# avr_switch_v09.net
KiCad netlist of a schematic drawn in EAGLE
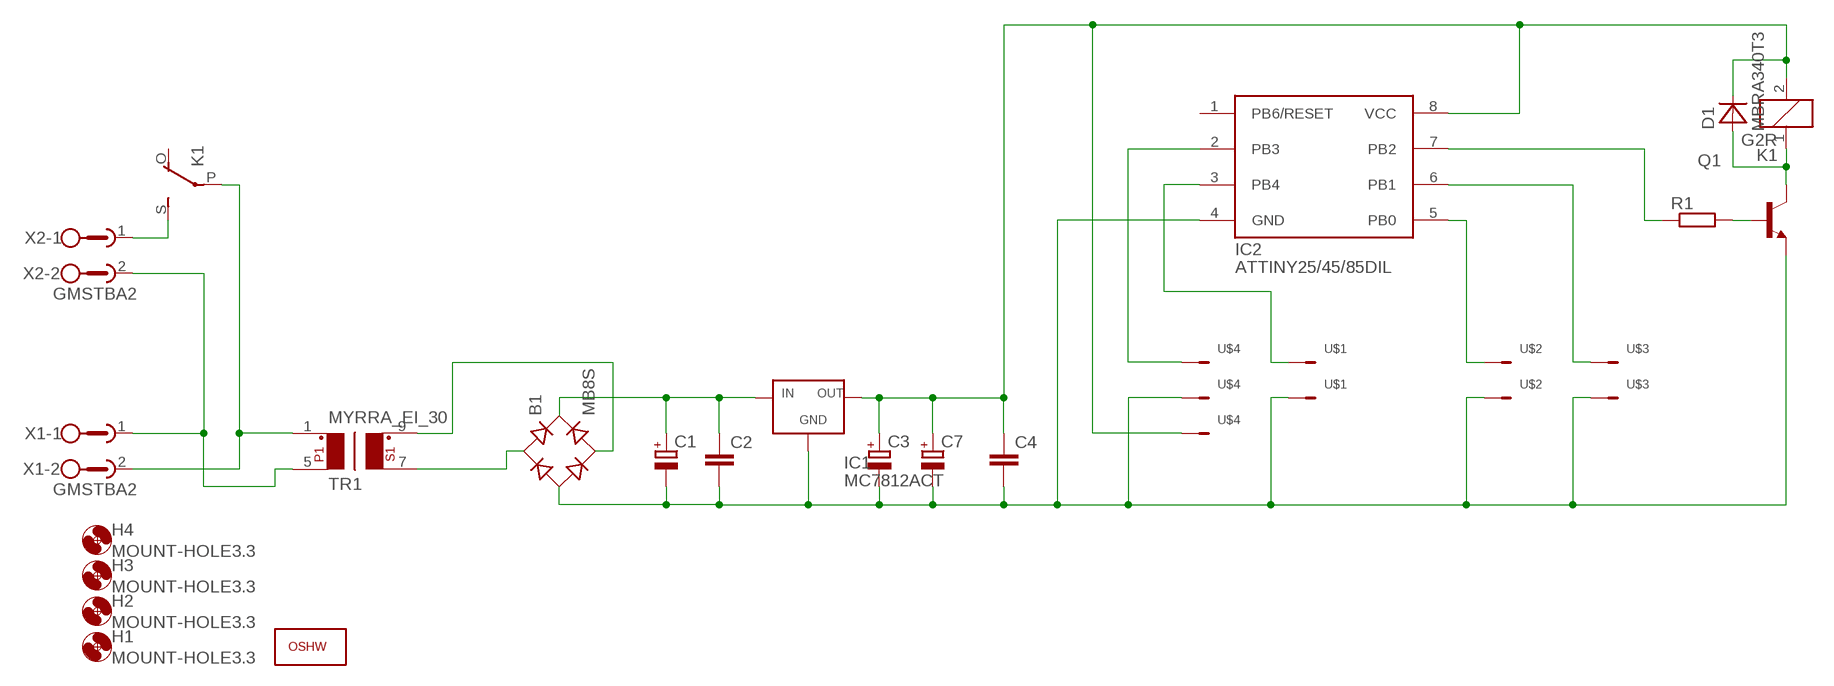
[diagram p0: schematic, sheet 1]

(export (version "E")
  (design (tool "Eeschema 10.0.6"))
  (components
    (comp (ref "B1")
      (value "MB8S")
      (footprint "eagle-import:SOIC-4")
      (libsource (lib "eagle-import") (part "MBS8"))
    )
    (comp (ref "C1")
      (value "CPOL-EUE5-10.5")
      (footprint "eagle-import:E5-10,5")
      (libsource (lib "eagle-import") (part "CPOL-EUE5-10.5"))
    )
    (comp (ref "C2")
      (value "C-EUC0805")
      (footprint "eagle-import:C0805")
      (libsource (lib "eagle-import") (part "C-EUC0805"))
    )
    (comp (ref "C3")
      (value "CPOL-EUCT6032")
      (footprint "eagle-import:CT6032")
      (libsource (lib "eagle-import") (part "CPOL-EUCT6032"))
    )
    (comp (ref "C4")
      (value "C-EUC0805")
      (footprint "eagle-import:C0805")
      (libsource (lib "eagle-import") (part "C-EUC0805"))
    )
    (comp (ref "C7")
      (value "CPOL-EUD/7343-31W")
      (footprint "eagle-import:D_7343-31W")
      (libsource (lib "eagle-import") (part "CPOL-EUD/7343-31W"))
    )
    (comp (ref "D1")
      (value "MBRA340T3")
      (footprint "eagle-import:SMA")
      (libsource (lib "eagle-import") (part "MBRA340T3"))
    )
    (comp (ref "H1")
      (value "MOUNT-HOLE3.3")
      (footprint "eagle-import:3,3")
      (libsource (lib "eagle-import") (part "MOUNT-HOLE3.3"))
    )
    (comp (ref "H2")
      (value "MOUNT-HOLE3.3")
      (footprint "eagle-import:3,3")
      (libsource (lib "eagle-import") (part "MOUNT-HOLE3.3"))
    )
    (comp (ref "H3")
      (value "MOUNT-HOLE3.3")
      (footprint "eagle-import:3,3")
      (libsource (lib "eagle-import") (part "MOUNT-HOLE3.3"))
    )
    (comp (ref "H4")
      (value "MOUNT-HOLE3.3")
      (footprint "eagle-import:3,3")
      (libsource (lib "eagle-import") (part "MOUNT-HOLE3.3"))
    )
    (comp (ref "IC1")
      (value "MC7812ACT")
      (footprint "eagle-import:TO220V")
      (libsource (lib "eagle-import") (part "MC7812ACT"))
    )
    (comp (ref "IC2")
      (value "ATTINY25/45/85DIL")
      (footprint "eagle-import:DIL08")
      (libsource (lib "eagle-import") (part "ATTINY25/45/85DIL"))
    )
    (comp (ref "K1")
      (value "G2R")
      (footprint "eagle-import:G2R")
      (libsource (lib "eagle-import") (part "G2R"))
    )
    (comp (ref "Q1")
      (value "BC548-NPN-TO92-CBE")
      (footprint "eagle-import:TO92-CBE")
      (libsource (lib "eagle-import") (part "-NPN-TO92-CBEBC548"))
    )
    (comp (ref "R1")
      (value "R-EU_R1206")
      (footprint "eagle-import:R1206")
      (libsource (lib "eagle-import") (part "R-EU_R1206"))
    )
    (comp (ref "TR1")
      (value "MYRRA_EI_30")
      (footprint "eagle-import:MYRRA-EI30")
      (libsource (lib "eagle-import") (part "MYRRA_EI_30"))
    )
    (comp (ref "U$1")
      (value "MOLEX-VERT-KK-2-")
      (footprint "eagle-import:MOLEX-KK-VERT-2PIN")
      (libsource (lib "eagle-import") (part "MOLEX-VERT-KK-2-"))
    )
    (comp (ref "U$2")
      (value "MOLEX-VERT-KK-2-")
      (footprint "eagle-import:MOLEX-KK-VERT-2PIN")
      (libsource (lib "eagle-import") (part "MOLEX-VERT-KK-2-"))
    )
    (comp (ref "U$3")
      (value "MOLEX-VERT-KK-2-")
      (footprint "eagle-import:MOLEX-KK-VERT-2PIN")
      (libsource (lib "eagle-import") (part "MOLEX-VERT-KK-2-"))
    )
    (comp (ref "U$4")
      (value "MOLEX-VERT-KK-3-3PIN")
      (footprint "eagle-import:MOLEX-KK-VERT-3PIN")
      (libsource (lib "eagle-import") (part "MOLEX-VERT-KK-3-3PIN"))
    )
    (comp (ref "U$5")
      (value "OSHWOSHW_TOP")
      (footprint "eagle-import:OSHW_F")
      (libsource (lib "eagle-import") (part "OSHWOSHW_TOP"))
    )
    (comp (ref "X1")
      (value "GMSTBA2")
      (footprint "eagle-import:GMSTBA2")
      (fields (field (name "MF") "FARNELL") (field (name "MPN") "1757242"))
      (libsource (lib "eagle-import") (part "GMSTBA2"))
    )
    (comp (ref "X2")
      (value "GMSTBA2")
      (footprint "eagle-import:GMSTBA2")
      (fields (field (name "MF") "FARNELL") (field (name "MPN") "1757242"))
      (libsource (lib "eagle-import") (part "GMSTBA2"))
    )
  )
  (nets
    (net (code "1") (name "Net-(B1-AC1)") (class "Default")
      (node (ref "B1") (pin "~1") (pinfunction "AC1_~1") (pintype "passive"))
      (node (ref "TR1") (pin "7") (pinfunction "7_7") (pintype "passive"))
    )
    (net (code "2") (name "Net-(B1-AC2)") (class "Default")
      (node (ref "B1") (pin "~2") (pinfunction "AC2_~2") (pintype "passive"))
      (node (ref "TR1") (pin "9") (pinfunction "9_9") (pintype "passive"))
    )
    (net (code "3") (name "Net-(D1-PadA)") (class "Default")
      (node (ref "D1") (pin "A") (pinfunction "A_A") (pintype "passive"))
      (node (ref "K1") (pin "1") (pinfunction "1_1") (pintype "passive"))
      (node (ref "Q1") (pin "C") (pinfunction "C_C") (pintype "passive"))
    )
    (net (code "4") (name "Net-(IC1-GND)") (class "Default")
      (node (ref "B1") (pin "-") (pinfunction "-_-") (pintype "passive"))
      (node (ref "C1") (pin "-") (pinfunction "-_-") (pintype "passive"))
      (node (ref "C2") (pin "2") (pinfunction "2_2") (pintype "passive"))
      (node (ref "C3") (pin "-") (pinfunction "-_-") (pintype "passive"))
      (node (ref "C4") (pin "2") (pinfunction "2_2") (pintype "passive"))
      (node (ref "C7") (pin "-") (pinfunction "-_-") (pintype "passive"))
      (node (ref "IC1") (pin "2") (pinfunction "GND_2") (pintype "bidirectional"))
      (node (ref "IC2") (pin "4") (pinfunction "GND_4") (pintype "bidirectional"))
      (node (ref "Q1") (pin "E") (pinfunction "E_E") (pintype "passive"))
      (node (ref "U$1") (pin "1") (pinfunction "P$1_1") (pintype "bidirectional"))
      (node (ref "U$2") (pin "1") (pinfunction "P$1_1") (pintype "bidirectional"))
      (node (ref "U$3") (pin "1") (pinfunction "P$1_1") (pintype "bidirectional"))
      (node (ref "U$4") (pin "2") (pinfunction "P$1_2") (pintype "bidirectional"))
    )
    (net (code "5") (name "Net-(IC1-IN)") (class "Default")
      (node (ref "B1") (pin "+") (pinfunction "+_+") (pintype "passive"))
      (node (ref "C1") (pin "+") (pinfunction "+_+") (pintype "passive"))
      (node (ref "C2") (pin "1") (pinfunction "1_1") (pintype "passive"))
      (node (ref "IC1") (pin "1") (pinfunction "IN_1") (pintype "bidirectional"))
    )
    (net (code "6") (name "Net-(IC1-OUT)") (class "Default")
      (node (ref "C3") (pin "+") (pinfunction "+_+") (pintype "passive"))
      (node (ref "C4") (pin "1") (pinfunction "1_1") (pintype "passive"))
      (node (ref "C7") (pin "+") (pinfunction "+_+") (pintype "passive"))
      (node (ref "D1") (pin "C") (pinfunction "C_C") (pintype "passive"))
      (node (ref "IC1") (pin "3") (pinfunction "OUT_3") (pintype "bidirectional"))
      (node (ref "IC2") (pin "8") (pinfunction "VCC_8") (pintype "bidirectional"))
      (node (ref "K1") (pin "2") (pinfunction "2_2") (pintype "passive"))
      (node (ref "U$4") (pin "1") (pinfunction "P$1_1") (pintype "bidirectional"))
    )
    (net (code "7") (name "Net-(IC2-PB0)") (class "Default")
      (node (ref "IC2") (pin "5") (pinfunction "PB0_5") (pintype "bidirectional"))
      (node (ref "U$2") (pin "2") (pinfunction "P$1_2") (pintype "bidirectional"))
    )
    (net (code "8") (name "Net-(IC2-PB1)") (class "Default")
      (node (ref "IC2") (pin "6") (pinfunction "PB1_6") (pintype "bidirectional"))
      (node (ref "U$3") (pin "2") (pinfunction "P$1_2") (pintype "bidirectional"))
    )
    (net (code "9") (name "Net-(IC2-PB2)") (class "Default")
      (node (ref "IC2") (pin "7") (pinfunction "PB2_7") (pintype "bidirectional"))
      (node (ref "R1") (pin "1") (pinfunction "1_1") (pintype "passive"))
    )
    (net (code "10") (name "Net-(IC2-PB3)") (class "Default")
      (node (ref "IC2") (pin "2") (pinfunction "PB3_2") (pintype "bidirectional"))
      (node (ref "U$4") (pin "3") (pinfunction "P$1_3") (pintype "bidirectional"))
    )
    (net (code "11") (name "Net-(IC2-PB4)") (class "Default")
      (node (ref "IC2") (pin "3") (pinfunction "PB4_3") (pintype "bidirectional"))
      (node (ref "U$1") (pin "2") (pinfunction "P$1_2") (pintype "bidirectional"))
    )
    (net (code "12") (name "Net-(K1-PadS)") (class "Default")
      (node (ref "K1") (pin "S") (pinfunction "S_S") (pintype "passive"))
      (node (ref "X2") (pin "1") (pinfunction "1_1") (pintype "passive"))
    )
    (net (code "13") (name "Net-(Q1-PadB)") (class "Default")
      (node (ref "Q1") (pin "B") (pinfunction "B_B") (pintype "passive"))
      (node (ref "R1") (pin "2") (pinfunction "2_2") (pintype "passive"))
    )
    (net (code "14") (name "Net-(X1B-1)") (class "Default")
      (node (ref "K1") (pin "P") (pinfunction "P_P") (pintype "passive"))
      (node (ref "TR1") (pin "1") (pinfunction "1_1") (pintype "passive"))
      (node (ref "X1") (pin "2") (pinfunction "1_2") (pintype "passive"))
    )
    (net (code "15") (name "Net-(X2B-1)") (class "Default")
      (node (ref "TR1") (pin "5") (pinfunction "5_5") (pintype "passive"))
      (node (ref "X1") (pin "1") (pinfunction "1_1") (pintype "passive"))
      (node (ref "X2") (pin "2") (pinfunction "1_2") (pintype "passive"))
    )
    (net (code "16") (name "unconnected-(IC2-PB6{slash}RESET-Pad1)") (class "Default")
      (node (ref "IC2") (pin "1") (pinfunction "PB6/RESET_1") (pintype "bidirectional"))
    )
    (net (code "17") (name "unconnected-(K1-PadO)") (class "Default")
      (node (ref "K1") (pin "O") (pinfunction "O_O") (pintype "passive"))
    )
  )
)
